# photo_transitor.net
KiCad netlist of a schematic drawn in EAGLE
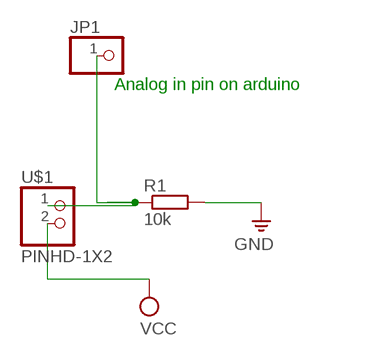
[diagram p0: schematic, sheet 1]

(export (version "E")
  (design (tool "Eeschema 10.0.6"))
  (components
    (comp (ref "JP1")
      (value "PINHD-1X1")
      (footprint "eagle-import:1X01")
      (libsource (lib "eagle-import") (part "PINHD-1X1"))
    )
    (comp (ref "R1")
      (value "10k")
      (footprint "eagle-import:R1206")
      (libsource (lib "eagle-import") (part "RESISTOR1206"))
    )
    (comp (ref "U$1")
      (value "PINHD-1X2")
      (footprint "eagle-import:1X02")
      (libsource (lib "eagle-import") (part "PINHD-1X2"))
    )
  )
  (nets
    (net (code "1") (name "GND") (class "Default")
      (node (ref "R1") (pin "2") (pinfunction "2_2") (pintype "passive"))
    )
    (net (code "2") (name "Net-(JP1-Pad1)") (class "Default")
      (node (ref "JP1") (pin "1") (pinfunction "1_1") (pintype "passive"))
      (node (ref "R1") (pin "1") (pinfunction "1_1") (pintype "passive"))
      (node (ref "U$1") (pin "1") (pinfunction "1_1") (pintype "passive"))
    )
    (net (code "3") (name "VCC") (class "Default")
      (node (ref "U$1") (pin "2") (pinfunction "2_2") (pintype "passive"))
    )
  )
)
